# TSH82_Configurable_Op_Amp_Board.net
KiCad netlist of a schematic drawn in EAGLE
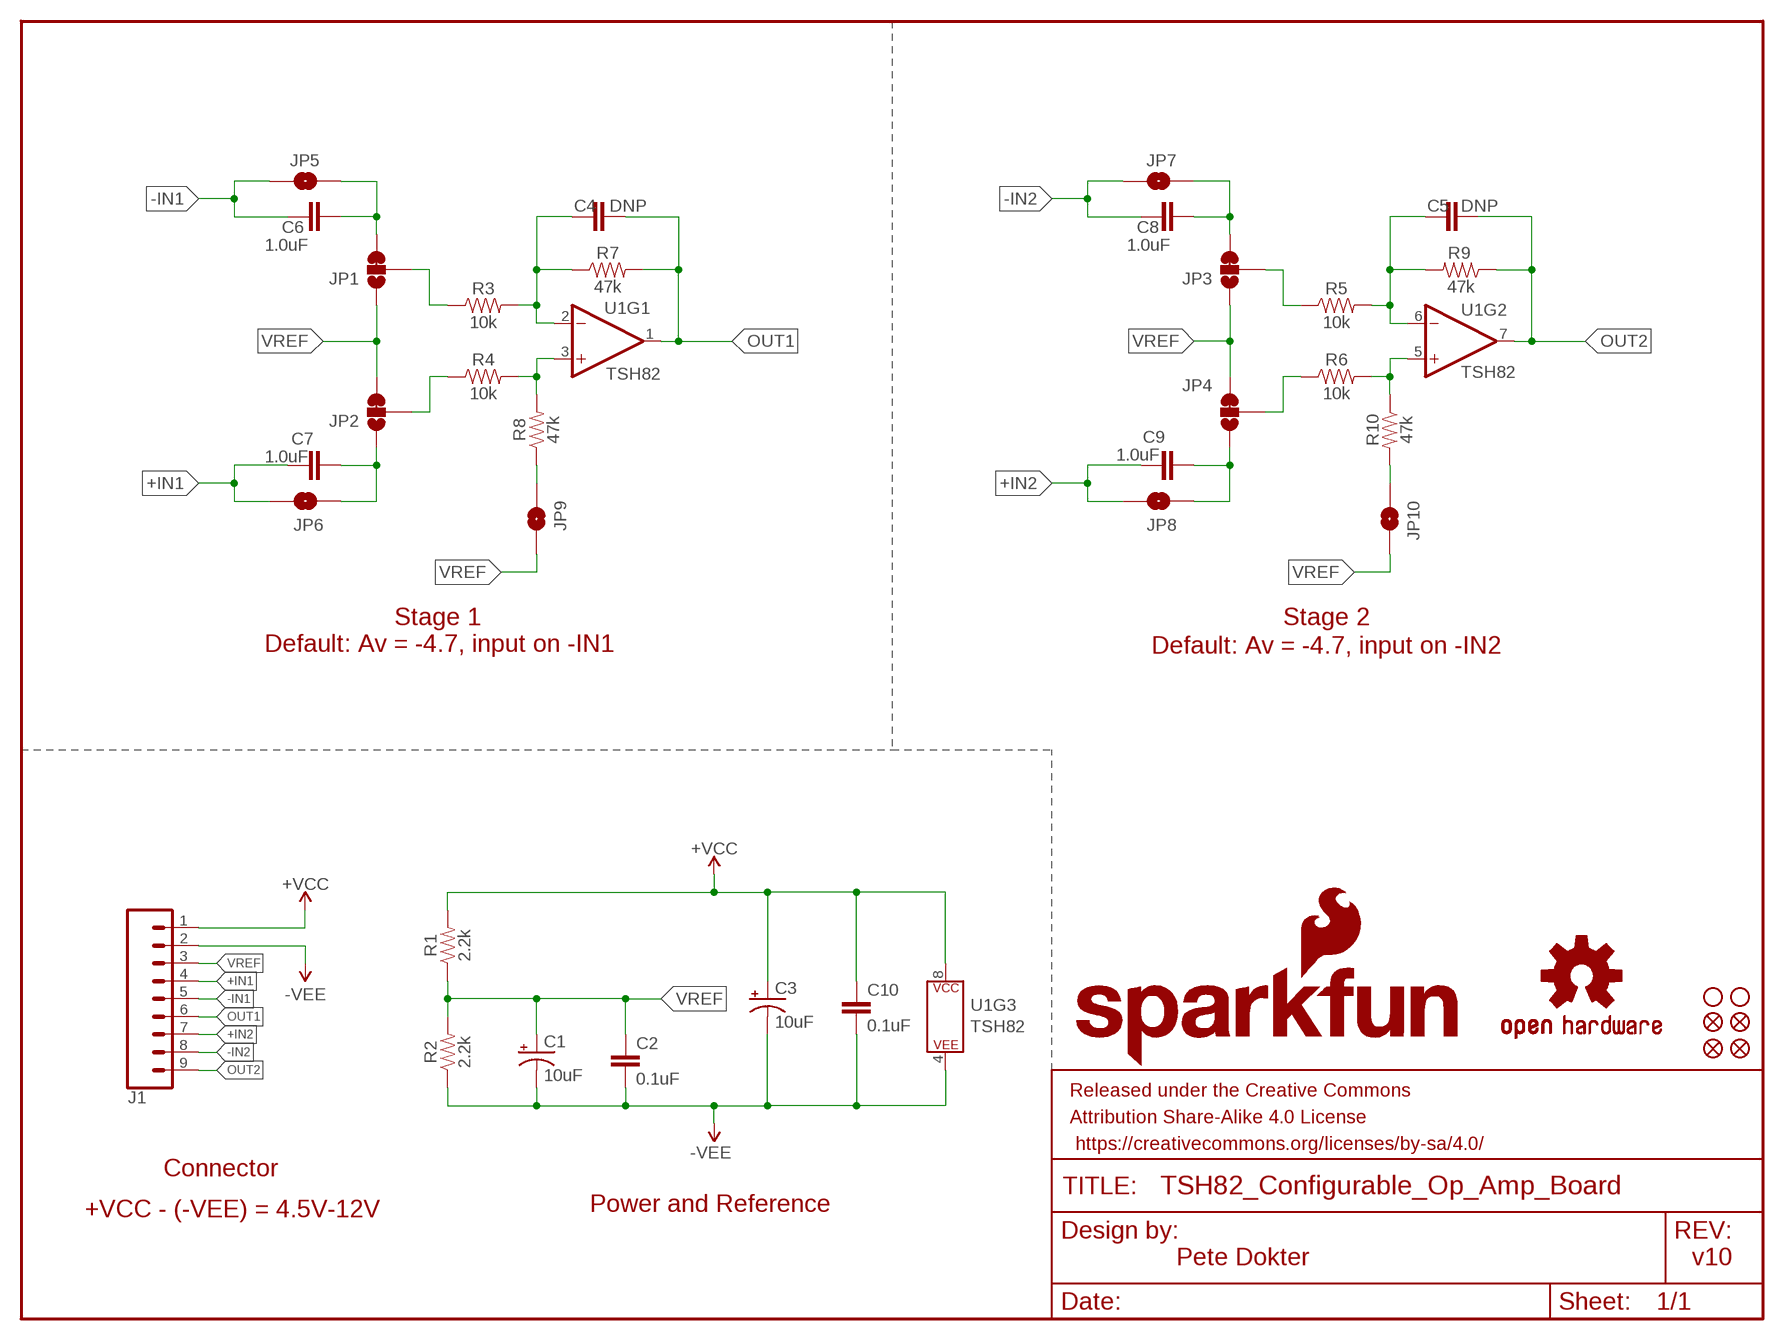
[diagram p0: schematic, sheet 1]

(export (version "E")
  (design (tool "Eeschema 10.0.6"))
  (components
    (comp (ref "C1")
      (value "10uF")
      (footprint "eagle-import:EIA3216")
      (libsource (lib "eagle-import") (part "10UF-POLAR-EIA3216-16V-10%(TANT)"))
    )
    (comp (ref "C2")
      (value "0.1uF")
      (footprint "eagle-import:0603")
      (libsource (lib "eagle-import") (part "0.1UF-0603-25V-(+80/-20%)"))
    )
    (comp (ref "C3")
      (value "10uF")
      (footprint "eagle-import:EIA3216")
      (libsource (lib "eagle-import") (part "10UF-POLAR-EIA3216-16V-10%(TANT)"))
    )
    (comp (ref "C4")
      (value "DNP")
      (footprint "eagle-import:0603")
      (libsource (lib "eagle-import") (part "1.0PF-0603-50V-25%"))
    )
    (comp (ref "C5")
      (value "DNP")
      (footprint "eagle-import:0603")
      (libsource (lib "eagle-import") (part "1.0PF-0603-50V-25%"))
    )
    (comp (ref "C6")
      (value "1.0uF")
      (footprint "eagle-import:0603")
      (libsource (lib "eagle-import") (part "1.0UF-0603-16V-10%"))
    )
    (comp (ref "C7")
      (value "1.0uF")
      (footprint "eagle-import:0603")
      (libsource (lib "eagle-import") (part "1.0UF-0603-16V-10%"))
    )
    (comp (ref "C8")
      (value "1.0uF")
      (footprint "eagle-import:0603")
      (libsource (lib "eagle-import") (part "1.0UF-0603-16V-10%"))
    )
    (comp (ref "C9")
      (value "1.0uF")
      (footprint "eagle-import:0603")
      (libsource (lib "eagle-import") (part "1.0UF-0603-16V-10%"))
    )
    (comp (ref "C10")
      (value "0.1uF")
      (footprint "eagle-import:0603")
      (libsource (lib "eagle-import") (part "0.1UF-0603-25V-(+80/-20%)"))
    )
    (comp (ref "FD1")
      (value "FIDUCIALUFIDUCIAL")
      (footprint "eagle-import:FIDUCIAL-MICRO")
      (libsource (lib "eagle-import") (part "FIDUCIALUFIDUCIAL"))
    )
    (comp (ref "FD2")
      (value "FIDUCIALUFIDUCIAL")
      (footprint "eagle-import:FIDUCIAL-MICRO")
      (libsource (lib "eagle-import") (part "FIDUCIALUFIDUCIAL"))
    )
    (comp (ref "FD3")
      (value "FIDUCIALUFIDUCIAL")
      (footprint "eagle-import:FIDUCIAL-MICRO")
      (libsource (lib "eagle-import") (part "FIDUCIALUFIDUCIAL"))
    )
    (comp (ref "FD4")
      (value "FIDUCIALUFIDUCIAL")
      (footprint "eagle-import:FIDUCIAL-MICRO")
      (libsource (lib "eagle-import") (part "FIDUCIALUFIDUCIAL"))
    )
    (comp (ref "FRAME1")
      (value "FRAME-LETTER")
      (footprint "eagle-import:CREATIVE_COMMONS")
      (libsource (lib "eagle-import") (part "FRAME-LETTER"))
    )
    (comp (ref "H1")
      (value "STAND-OFF")
      (footprint "eagle-import:STAND-OFF")
      (libsource (lib "eagle-import") (part "STAND-OFF"))
    )
    (comp (ref "H2")
      (value "STAND-OFF")
      (footprint "eagle-import:STAND-OFF")
      (libsource (lib "eagle-import") (part "STAND-OFF"))
    )
    (comp (ref "J1")
      (value "CONN_09NO_SILK")
      (footprint "eagle-import:1X09_NO_SILK")
      (libsource (lib "eagle-import") (part "CONN_09NO_SILK"))
    )
    (comp (ref "JP1")
      (value "JUMPER-SMT_3_1-NC_TRACE_SILK")
      (footprint "eagle-import:SMT-JUMPER_3_1-NC_TRACE_SILK")
      (libsource (lib "eagle-import") (part "JUMPER-SMT_3_1-NC_TRACE_SILK"))
    )
    (comp (ref "JP2")
      (value "JUMPER-SMT_3_1-NC_TRACE_SILK")
      (footprint "eagle-import:SMT-JUMPER_3_1-NC_TRACE_SILK")
      (libsource (lib "eagle-import") (part "JUMPER-SMT_3_1-NC_TRACE_SILK"))
    )
    (comp (ref "JP3")
      (value "JUMPER-SMT_3_1-NC_TRACE_SILK")
      (footprint "eagle-import:SMT-JUMPER_3_1-NC_TRACE_SILK")
      (libsource (lib "eagle-import") (part "JUMPER-SMT_3_1-NC_TRACE_SILK"))
    )
    (comp (ref "JP4")
      (value "JUMPER-SMT_3_1-NC_TRACE_SILK")
      (footprint "eagle-import:SMT-JUMPER_3_1-NC_TRACE_SILK")
      (libsource (lib "eagle-import") (part "JUMPER-SMT_3_1-NC_TRACE_SILK"))
    )
    (comp (ref "JP5")
      (value "JUMPER-SMT_2_NO_SILK")
      (footprint "eagle-import:SMT-JUMPER_2_NO_SILK")
      (libsource (lib "eagle-import") (part "JUMPER-SMT_2_NO_SILK"))
    )
    (comp (ref "JP6")
      (value "JUMPER-SMT_2_NO_SILK")
      (footprint "eagle-import:SMT-JUMPER_2_NO_SILK")
      (libsource (lib "eagle-import") (part "JUMPER-SMT_2_NO_SILK"))
    )
    (comp (ref "JP7")
      (value "JUMPER-SMT_2_NO_SILK")
      (footprint "eagle-import:SMT-JUMPER_2_NO_SILK")
      (libsource (lib "eagle-import") (part "JUMPER-SMT_2_NO_SILK"))
    )
    (comp (ref "JP8")
      (value "JUMPER-SMT_2_NO_SILK")
      (footprint "eagle-import:SMT-JUMPER_2_NO_SILK")
      (libsource (lib "eagle-import") (part "JUMPER-SMT_2_NO_SILK"))
    )
    (comp (ref "JP9")
      (value "JUMPER-SMT_2_NO_SILK")
      (footprint "eagle-import:SMT-JUMPER_2_NO_SILK")
      (libsource (lib "eagle-import") (part "JUMPER-SMT_2_NO_SILK"))
    )
    (comp (ref "JP10")
      (value "JUMPER-SMT_2_NO_SILK")
      (footprint "eagle-import:SMT-JUMPER_2_NO_SILK")
      (libsource (lib "eagle-import") (part "JUMPER-SMT_2_NO_SILK"))
    )
    (comp (ref "LOGO1")
      (value "SFE_LOGO_FLAME.2_INCH")
      (footprint "eagle-import:SFE_LOGO_FLAME_.2")
      (libsource (lib "eagle-import") (part "SFE_LOGO_FLAME.2_INCH"))
    )
    (comp (ref "LOGO2")
      (value "SFE_LOGO_NAME_FLAME.1_INCH")
      (footprint "eagle-import:SFE_LOGO_NAME_FLAME_.1")
      (libsource (lib "eagle-import") (part "SFE_LOGO_NAME_FLAME.1_INCH"))
    )
    (comp (ref "LOGO3")
      (value "OSHW-LOGOS")
      (footprint "eagle-import:OSHW-LOGO-S")
      (libsource (lib "eagle-import") (part "OSHW-LOGOS"))
    )
    (comp (ref "R1")
      (value "2.2k")
      (footprint "eagle-import:0603")
      (libsource (lib "eagle-import") (part "2.2KOHM-0603-1/10W-1%"))
    )
    (comp (ref "R2")
      (value "2.2k")
      (footprint "eagle-import:0603")
      (libsource (lib "eagle-import") (part "2.2KOHM-0603-1/10W-1%"))
    )
    (comp (ref "R3")
      (value "10k")
      (footprint "eagle-import:0603")
      (libsource (lib "eagle-import") (part "10KOHM-0603-1/10W-1%"))
    )
    (comp (ref "R4")
      (value "10k")
      (footprint "eagle-import:0603")
      (libsource (lib "eagle-import") (part "10KOHM-0603-1/10W-1%"))
    )
    (comp (ref "R5")
      (value "10k")
      (footprint "eagle-import:0603")
      (libsource (lib "eagle-import") (part "10KOHM-0603-1/10W-1%"))
    )
    (comp (ref "R6")
      (value "10k")
      (footprint "eagle-import:0603")
      (libsource (lib "eagle-import") (part "10KOHM-0603-1/10W-1%"))
    )
    (comp (ref "R7")
      (value "47k")
      (footprint "eagle-import:0603")
      (libsource (lib "eagle-import") (part "47KOHM-0603-1/10W-1%"))
    )
    (comp (ref "R8")
      (value "47k")
      (footprint "eagle-import:0603")
      (libsource (lib "eagle-import") (part "47KOHM-0603-1/10W-1%"))
    )
    (comp (ref "R9")
      (value "47k")
      (footprint "eagle-import:0603")
      (libsource (lib "eagle-import") (part "47KOHM-0603-1/10W-1%"))
    )
    (comp (ref "R10")
      (value "47k")
      (footprint "eagle-import:0603")
      (libsource (lib "eagle-import") (part "47KOHM-0603-1/10W-1%"))
    )
    (comp (ref "U1")
      (value "TSH82")
      (footprint "eagle-import:SO08")
      (libsource (lib "eagle-import") (part "TSH82"))
    )
  )
  (nets
    (net (code "1") (name "+IN1") (class "Default")
      (node (ref "C7") (pin "1") (pinfunction "1_1") (pintype "passive"))
      (node (ref "J1") (pin "4") (pinfunction "4_4") (pintype "passive"))
      (node (ref "JP6") (pin "2") (pinfunction "2_2") (pintype "passive"))
    )
    (net (code "2") (name "+IN2") (class "Default")
      (node (ref "C9") (pin "1") (pinfunction "1_1") (pintype "passive"))
      (node (ref "J1") (pin "7") (pinfunction "7_7") (pintype "passive"))
      (node (ref "JP8") (pin "2") (pinfunction "2_2") (pintype "passive"))
    )
    (net (code "3") (name "+VCC") (class "Default")
      (node (ref "C10") (pin "1") (pinfunction "1_1") (pintype "passive"))
      (node (ref "C3") (pin "+") (pinfunction "+_+") (pintype "passive"))
      (node (ref "J1") (pin "1") (pinfunction "1_1") (pintype "passive"))
      (node (ref "R1") (pin "2") (pinfunction "2_2") (pintype "passive"))
      (node (ref "U1") (pin "8") (pinfunction "P$V+_8") (pintype "bidirectional"))
    )
    (net (code "4") (name "-IN1") (class "Default")
      (node (ref "C6") (pin "1") (pinfunction "1_1") (pintype "passive"))
      (node (ref "J1") (pin "5") (pinfunction "5_5") (pintype "passive"))
      (node (ref "JP5") (pin "2") (pinfunction "2_2") (pintype "passive"))
    )
    (net (code "5") (name "-IN2") (class "Default")
      (node (ref "C8") (pin "1") (pinfunction "1_1") (pintype "passive"))
      (node (ref "J1") (pin "8") (pinfunction "8_8") (pintype "passive"))
      (node (ref "JP7") (pin "2") (pinfunction "2_2") (pintype "passive"))
    )
    (net (code "6") (name "-VEE") (class "Default")
      (node (ref "C1") (pin "-") (pinfunction "-_-") (pintype "passive"))
      (node (ref "C10") (pin "2") (pinfunction "2_2") (pintype "passive"))
      (node (ref "C2") (pin "2") (pinfunction "2_2") (pintype "passive"))
      (node (ref "C3") (pin "-") (pinfunction "-_-") (pintype "passive"))
      (node (ref "J1") (pin "2") (pinfunction "2_2") (pintype "passive"))
      (node (ref "R2") (pin "1") (pinfunction "1_1") (pintype "passive"))
      (node (ref "U1") (pin "4") (pinfunction "P$V-_4") (pintype "bidirectional"))
    )
    (net (code "7") (name "Net-(C6-Pad2)") (class "Default")
      (node (ref "C6") (pin "2") (pinfunction "2_2") (pintype "passive"))
      (node (ref "JP1") (pin "3") (pinfunction "3_3") (pintype "passive"))
      (node (ref "JP5") (pin "1") (pinfunction "1_1") (pintype "passive"))
    )
    (net (code "8") (name "Net-(C7-Pad2)") (class "Default")
      (node (ref "C7") (pin "2") (pinfunction "2_2") (pintype "passive"))
      (node (ref "JP2") (pin "1") (pinfunction "1_1") (pintype "passive"))
      (node (ref "JP6") (pin "1") (pinfunction "1_1") (pintype "passive"))
    )
    (net (code "9") (name "Net-(C8-Pad2)") (class "Default")
      (node (ref "C8") (pin "2") (pinfunction "2_2") (pintype "passive"))
      (node (ref "JP3") (pin "3") (pinfunction "3_3") (pintype "passive"))
      (node (ref "JP7") (pin "1") (pinfunction "1_1") (pintype "passive"))
    )
    (net (code "10") (name "Net-(C9-Pad2)") (class "Default")
      (node (ref "C9") (pin "2") (pinfunction "2_2") (pintype "passive"))
      (node (ref "JP4") (pin "1") (pinfunction "1_1") (pintype "passive"))
      (node (ref "JP8") (pin "1") (pinfunction "1_1") (pintype "passive"))
    )
    (net (code "11") (name "Net-(JP1-Pad2)") (class "Default")
      (node (ref "JP1") (pin "2") (pinfunction "2_2") (pintype "passive"))
      (node (ref "R3") (pin "1") (pinfunction "1_1") (pintype "passive"))
    )
    (net (code "12") (name "Net-(JP2-Pad2)") (class "Default")
      (node (ref "JP2") (pin "2") (pinfunction "2_2") (pintype "passive"))
      (node (ref "R4") (pin "1") (pinfunction "1_1") (pintype "passive"))
    )
    (net (code "13") (name "Net-(JP3-Pad2)") (class "Default")
      (node (ref "JP3") (pin "2") (pinfunction "2_2") (pintype "passive"))
      (node (ref "R5") (pin "1") (pinfunction "1_1") (pintype "passive"))
    )
    (net (code "14") (name "Net-(JP4-Pad2)") (class "Default")
      (node (ref "JP4") (pin "2") (pinfunction "2_2") (pintype "passive"))
      (node (ref "R6") (pin "1") (pinfunction "1_1") (pintype "passive"))
    )
    (net (code "15") (name "Net-(JP9-Pad1)") (class "Default")
      (node (ref "JP9") (pin "1") (pinfunction "1_1") (pintype "passive"))
      (node (ref "R8") (pin "1") (pinfunction "1_1") (pintype "passive"))
    )
    (net (code "16") (name "Net-(JP10-Pad1)") (class "Default")
      (node (ref "JP10") (pin "1") (pinfunction "1_1") (pintype "passive"))
      (node (ref "R10") (pin "2") (pinfunction "2_2") (pintype "passive"))
    )
    (net (code "17") (name "Net-(U1A-+IN)") (class "Default")
      (node (ref "R4") (pin "2") (pinfunction "2_2") (pintype "passive"))
      (node (ref "R8") (pin "2") (pinfunction "2_2") (pintype "passive"))
      (node (ref "U1") (pin "3") (pinfunction "+IN_3") (pintype "input"))
    )
    (net (code "18") (name "Net-(U1A--IN)") (class "Default")
      (node (ref "C4") (pin "1") (pinfunction "1_1") (pintype "passive"))
      (node (ref "R3") (pin "2") (pinfunction "2_2") (pintype "passive"))
      (node (ref "R7") (pin "1") (pinfunction "1_1") (pintype "passive"))
      (node (ref "U1") (pin "2") (pinfunction "-IN_2") (pintype "input"))
    )
    (net (code "19") (name "Net-(U1B-+IN)") (class "Default")
      (node (ref "R10") (pin "1") (pinfunction "1_1") (pintype "passive"))
      (node (ref "R6") (pin "2") (pinfunction "2_2") (pintype "passive"))
      (node (ref "U1") (pin "5") (pinfunction "+IN_5") (pintype "input"))
    )
    (net (code "20") (name "Net-(U1B--IN)") (class "Default")
      (node (ref "C5") (pin "1") (pinfunction "1_1") (pintype "passive"))
      (node (ref "R5") (pin "2") (pinfunction "2_2") (pintype "passive"))
      (node (ref "R9") (pin "2") (pinfunction "2_2") (pintype "passive"))
      (node (ref "U1") (pin "6") (pinfunction "-IN_6") (pintype "input"))
    )
    (net (code "21") (name "OUT1") (class "Default")
      (node (ref "C4") (pin "2") (pinfunction "2_2") (pintype "passive"))
      (node (ref "J1") (pin "6") (pinfunction "6_6") (pintype "passive"))
      (node (ref "R7") (pin "2") (pinfunction "2_2") (pintype "passive"))
      (node (ref "U1") (pin "1") (pinfunction "OUT_1") (pintype "output"))
    )
    (net (code "22") (name "OUT2") (class "Default")
      (node (ref "C5") (pin "2") (pinfunction "2_2") (pintype "passive"))
      (node (ref "J1") (pin "9") (pinfunction "9_9") (pintype "passive"))
      (node (ref "R9") (pin "1") (pinfunction "1_1") (pintype "passive"))
      (node (ref "U1") (pin "7") (pinfunction "OUT_7") (pintype "output"))
    )
    (net (code "23") (name "VREF") (class "Default")
      (node (ref "C1") (pin "+") (pinfunction "+_+") (pintype "passive"))
      (node (ref "C2") (pin "1") (pinfunction "1_1") (pintype "passive"))
      (node (ref "J1") (pin "3") (pinfunction "3_3") (pintype "passive"))
      (node (ref "JP1") (pin "1") (pinfunction "1_1") (pintype "passive"))
      (node (ref "JP10") (pin "2") (pinfunction "2_2") (pintype "passive"))
      (node (ref "JP2") (pin "3") (pinfunction "3_3") (pintype "passive"))
      (node (ref "JP3") (pin "1") (pinfunction "1_1") (pintype "passive"))
      (node (ref "JP4") (pin "3") (pinfunction "3_3") (pintype "passive"))
      (node (ref "JP9") (pin "2") (pinfunction "2_2") (pintype "passive"))
      (node (ref "R1") (pin "1") (pinfunction "1_1") (pintype "passive"))
      (node (ref "R2") (pin "2") (pinfunction "2_2") (pintype "passive"))
    )
  )
)
